# H0AR4_Backend.net
KiCad netlist of a schematic drawn in Altium Designer
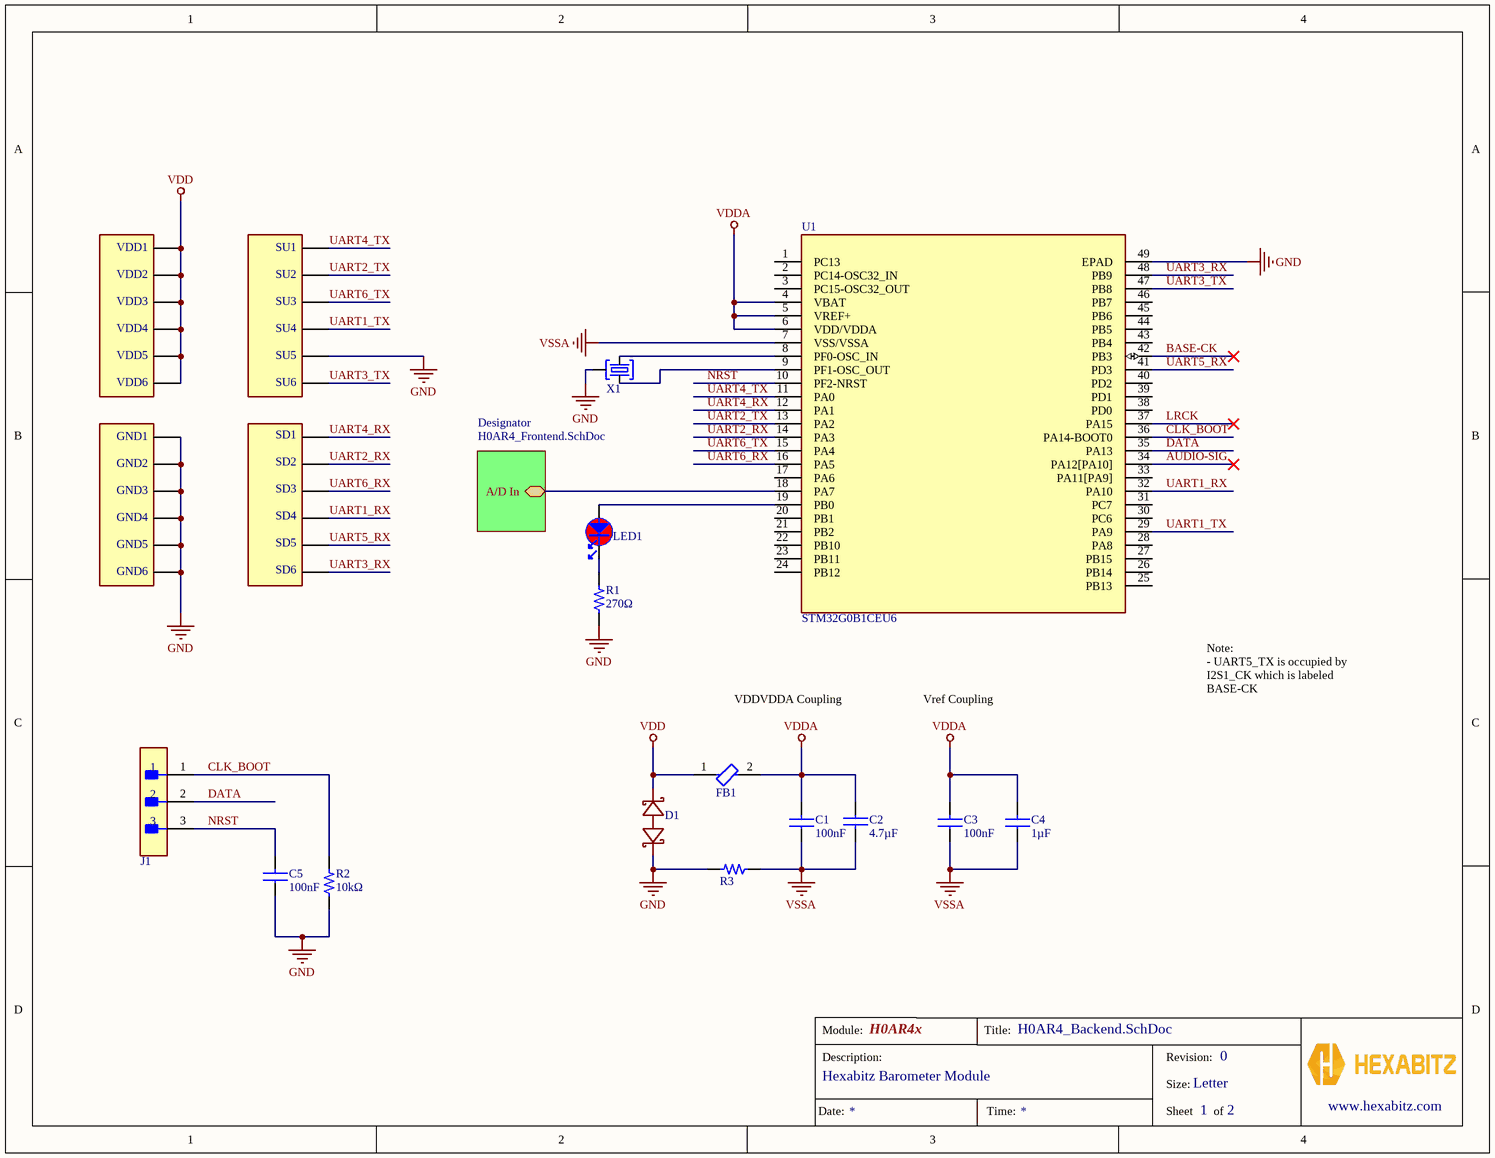
[diagram p0: H0AR4_Backend.SchDoc]

(export (version "E")
  (design (tool "Eeschema 10.0.6"))
  (components
    (comp (ref "C1")
      (value "100nF")
      (footprint "C0603")
      (fields
        (field (name "MANUFACTURER") "Samsung Electro-Mechanics")
        (field (name "MANUFACTURER PART NUMBER") "CL10B104KA8NNNC")
        (field (name "TOLERANCE") "10%")
      )
      (libsource (lib "Hexabitz Altium Library") (part "generic Capacitor"))
    )
    (comp (ref "C2")
      (value "4.7µF")
      (footprint "C0805")
      (fields
        (field (name "MANUFACTURER") "Samsung Electro-Mechanics")
        (field (name "MANUFACTURER PART NUMBER") "CL21X475KAQNNNE")
        (field (name "TOLERANCE") "10%")
      )
      (libsource (lib "Hexabitz Altium Library") (part "generic Capacitor"))
    )
    (comp (ref "C3")
      (value "100nF")
      (footprint "C0603")
      (fields
        (field (name "MANUFACTURER") "Samsung Electro-Mechanics")
        (field (name "MANUFACTURER PART NUMBER") "CL10B104KA8NNNC")
        (field (name "TOLERANCE") "10%")
      )
      (libsource (lib "Hexabitz Altium Library") (part "generic Capacitor"))
    )
    (comp (ref "C4")
      (value "1µF")
      (footprint "C0805")
      (description "Ceramic Capacitor, Ceramic, 16V, 10% +Tol, 10% -Tol, X7R, 15% TC, 1uF, Surface Mount, 0805")
      (fields
        (field (name "MANUFACTURER") "Yageo Group")
        (field (name "MANUFACTURER PART NUMBER") "CC0805KKX7R7BB105")
      )
      (libsource (lib "Hexabitz Altium Library") (part "generic Capacitor"))
    )
    (comp (ref "C5")
      (value "100nF")
      (footprint "C0603")
      (fields
        (field (name "MANUFACTURER") "Samsung Electro-Mechanics")
        (field (name "MANUFACTURER PART NUMBER") "CL10B104KA8NNNC")
        (field (name "TOLERANCE") "10%")
      )
      (libsource (lib "Hexabitz Altium Library") (part "generic Capacitor"))
    )
    (comp (ref "D1")
      (value "CDSOD323-T03SC")
      (footprint "SOD2513X114N")
      (description "A 3V, 350W, bi-directional, standard capacitance, SOD323 pkg TVS Diode ¦ Bourns CDSOD323-T03SC")
      (fields (field (name "MANUFACTURER") "Bourns"))
      (libsource (lib "Hexabitz Altium Library") (part "CDSOD323-T03SC"))
    )
    (comp (ref "FB1")
      (value "MMZ1608Y300B")
      (footprint "FP-MMZ1608-0_8-MFG")
      (description "Ferrite Beads 0603 30ohms 1500mA Signal Line AEC-Q200")
      (fields
        (field (name "MANUFACTURER") "TDK")
        (field (name "MANUFACTURER PART NUMBER") "MMZ1608Y300BTD25")
      )
      (libsource (lib "Hexabitz Altium Library") (part "MMZ1608Y300B"))
    )
    (comp (ref "GND1")
      (value "HEXABIT_UART_PORT")
      (footprint "HEXABIT_POWER_PORT_D")
      (libsource (lib "hexabitz_connectors.Library") (part "HEXABIT_POWER_PORT_D"))
    )
    (comp (ref "GND2")
      (value "HEXABIT_UART_PORT")
      (footprint "HEXABIT_POWER_PORT_D")
      (libsource (lib "hexabitz_connectors.Library") (part "HEXABIT_POWER_PORT_D"))
    )
    (comp (ref "GND3")
      (value "HEXABIT_UART_PORT")
      (footprint "HEXABIT_POWER_PORT_D")
      (libsource (lib "hexabitz_connectors.Library") (part "HEXABIT_POWER_PORT_D"))
    )
    (comp (ref "GND4")
      (value "HEXABIT_UART_PORT")
      (footprint "HEXABIT_POWER_PORT_D")
      (libsource (lib "hexabitz_connectors.Library") (part "HEXABIT_POWER_PORT_D"))
    )
    (comp (ref "GND5")
      (value "HEXABIT_UART_PORT")
      (footprint "HEXABIT_POWER_PORT_D")
      (libsource (lib "hexabitz_connectors.Library") (part "HEXABIT_POWER_PORT_D"))
    )
    (comp (ref "GND6")
      (value "HEXABIT_UART_PORT")
      (footprint "HEXABIT_POWER_PORT_D")
      (libsource (lib "hexabitz_connectors.Library") (part "HEXABIT_POWER_PORT_D"))
    )
    (comp (ref "J1")
      (value "TSW-103-14-G-S")
      (footprint "FP-TSW-103-14-G-S-MFG")
      (description "CONN HEADER VERT 3POS 2.54MM")
      (libsource (lib "Altium Content Vault") (part "cd3439d6ef35ae5d9b27ec4fdd3e828"))
    )
    (comp (ref "LED1")
      (value "VLMS1300-GS08")
      (footprint "FP-6_541-5092_01-4-MFG")
      (description "LED Uni-Color Super Red 639nm 2-Pin Chip 0603(1608Metric) T/R")
      (fields (field (name "MANUFACTURER") "Vishay Semiconductors"))
      (libsource (lib "Hexabitz Altium Library") (part "VLMS1300-GS08"))
    )
    (comp (ref "R1")
      (value "270Ω")
      (footprint "R0603")
      (description "Res Thick Film 0603 270 Ohm 5% 0.1W(1/10W) ±200ppm/C Pad SMD Automotive T/R")
      (fields
        (field (name "MANUFACTURER") "Panasonic")
        (field (name "MANUFACTURER PART NUMBER") "ERJ-3GEYJ271V")
      )
      (libsource (lib "") (part "generic Resistor_1"))
    )
    (comp (ref "R2")
      (value "10kΩ")
      (footprint "R0603")
      (description "100mW Thick Film Resistors ±100ppm/℃ ±1% 10kΩ 0603 Chip Resistor - Surface Mount ROHS")
      (fields
        (field (name "MANUFACTURER") "Yageo Group")
        (field (name "MANUFACTURER PART NUMBER") "RC0603FR-0710KL")
      )
      (libsource (lib "") (part "generic Resistor_2"))
    )
    (comp (ref "R3")
      (value "Manufacturer Part Number")
      (footprint "R0603")
      (libsource (lib "Hexabitz Altium Library") (part "generic Resistor"))
    )
    (comp (ref "SD1")
      (value "HEXABIT_UART_PORT")
      (footprint "HEXABIT_UART_PORT_D")
      (libsource (lib "hexabitz_connectors.Library") (part "HEXABIT_UART_PORT_D"))
    )
    (comp (ref "SD2")
      (value "HEXABIT_UART_PORT")
      (footprint "HEXABIT_UART_PORT_D")
      (libsource (lib "hexabitz_connectors.Library") (part "HEXABIT_UART_PORT_D"))
    )
    (comp (ref "SD3")
      (value "HEXABIT_UART_PORT")
      (footprint "HEXABIT_UART_PORT_D")
      (libsource (lib "hexabitz_connectors.Library") (part "HEXABIT_UART_PORT_D"))
    )
    (comp (ref "SD4")
      (value "HEXABIT_UART_PORT")
      (footprint "HEXABIT_UART_PORT_D")
      (libsource (lib "hexabitz_connectors.Library") (part "HEXABIT_UART_PORT_D"))
    )
    (comp (ref "SD5")
      (value "HEXABIT_UART_PORT")
      (footprint "HEXABIT_UART_PORT_D")
      (libsource (lib "hexabitz_connectors.Library") (part "HEXABIT_UART_PORT_D"))
    )
    (comp (ref "SD6")
      (value "HEXABIT_UART_PORT")
      (footprint "HEXABIT_UART_PORT_D")
      (libsource (lib "hexabitz_connectors.Library") (part "HEXABIT_UART_PORT_D"))
    )
    (comp (ref "SU1")
      (value "HEXABIT_UART_PORT")
      (footprint "HEXABIT_UART_PORT_U")
      (libsource (lib "hexabitz_connectors.Library") (part "HEXABIT_UART_PORT_U"))
    )
    (comp (ref "SU2")
      (value "HEXABIT_UART_PORT")
      (footprint "HEXABIT_UART_PORT_U")
      (libsource (lib "hexabitz_connectors.Library") (part "HEXABIT_UART_PORT_U"))
    )
    (comp (ref "SU3")
      (value "HEXABIT_UART_PORT")
      (footprint "HEXABIT_UART_PORT_U")
      (libsource (lib "hexabitz_connectors.Library") (part "HEXABIT_UART_PORT_U"))
    )
    (comp (ref "SU4")
      (value "HEXABIT_UART_PORT")
      (footprint "HEXABIT_UART_PORT_U")
      (libsource (lib "hexabitz_connectors.Library") (part "HEXABIT_UART_PORT_U"))
    )
    (comp (ref "SU5")
      (value "HEXABIT_UART_PORT")
      (footprint "HEXABIT_UART_PORT_U")
      (libsource (lib "hexabitz_connectors.Library") (part "HEXABIT_UART_PORT_U"))
    )
    (comp (ref "SU6")
      (value "HEXABIT_UART_PORT")
      (footprint "HEXABIT_UART_PORT_U")
      (libsource (lib "hexabitz_connectors.Library") (part "HEXABIT_UART_PORT_U"))
    )
    (comp (ref "U1")
      (value "STM32G0B1CEU6")
      (footprint "QFN50P700X700X65-49N-D")
      (description "MCU 32-bit ARM Cortex M0+ RISC 512KB Flash 1.8V/2.5V/3.3V 48-Pin UFQFPN EP Tray")
      (fields
        (field (name "MANUFACTURER") "STMicroelectronics")
        (field (name "MANUFACTURER PART NUMBER") "STM32G0B1CEU6")
      )
      (libsource (lib "Hexabitz Altium Library") (part "STM32G0B1CEU6"))
    )
    (comp (ref "VDD1")
      (value "HEXABIT_UART_PORT")
      (footprint "HEXABIT_POWER_PORT_U")
      (libsource (lib "hexabitz_connectors.Library") (part "HEXABIT_POWER_PORT_U"))
    )
    (comp (ref "VDD2")
      (value "HEXABIT_UART_PORT")
      (footprint "HEXABIT_POWER_PORT_U")
      (libsource (lib "hexabitz_connectors.Library") (part "HEXABIT_POWER_PORT_U"))
    )
    (comp (ref "VDD3")
      (value "HEXABIT_UART_PORT")
      (footprint "HEXABIT_POWER_PORT_U")
      (libsource (lib "hexabitz_connectors.Library") (part "HEXABIT_POWER_PORT_U"))
    )
    (comp (ref "VDD4")
      (value "HEXABIT_UART_PORT")
      (footprint "HEXABIT_POWER_PORT_U")
      (libsource (lib "hexabitz_connectors.Library") (part "HEXABIT_POWER_PORT_U"))
    )
    (comp (ref "VDD5")
      (value "HEXABIT_UART_PORT")
      (footprint "HEXABIT_POWER_PORT_U")
      (libsource (lib "hexabitz_connectors.Library") (part "HEXABIT_POWER_PORT_U"))
    )
    (comp (ref "VDD6")
      (value "HEXABIT_UART_PORT")
      (footprint "HEXABIT_POWER_PORT_U")
      (libsource (lib "hexabitz_connectors.Library") (part "HEXABIT_POWER_PORT_U"))
    )
    (comp (ref "X1")
      (value "CSTCE8M00G52Z-R0")
      (footprint "XTALL_CSTCE8M00G52")
      (description "Ceramic Resonator 8MHz ±0.5% (Tol) ±0.2% (Stability) 10pF 40Ohm 3-Pin CSMD T/R")
      (fields (field (name "MANUFACTURER") "Murata") (field (name "TOLERANCE") "0.5%"))
      (libsource (lib "Hexabitz Altium Library") (part "CSTCE8M00G52Z-R0"))
    )
  )
  (nets
    (net (code "1") (name "/AUDIO-SIG") (class "Default")
      (node (ref "U1") (pin "34") (pinfunction "PA12[PA10]_34") (pintype "passive+no_connect"))
    )
    (net (code "2") (name "/A{slash}D In") (class "Default")
      (node (ref "U1") (pin "18") (pinfunction "PA7_18") (pintype "passive"))
    )
    (net (code "3") (name "/BASE-CK") (class "Default")
      (node (ref "U1") (pin "42") (pinfunction "PB3_42") (pintype "bidirectional+no_connect"))
    )
    (net (code "4") (name "/CLK_BOOT") (class "Default")
      (node (ref "J1") (pin "1") (pinfunction "1_1") (pintype "passive"))
      (node (ref "R2") (pin "1") (pinfunction "1_1") (pintype "passive"))
      (node (ref "U1") (pin "36") (pinfunction "PA14-BOOT0_36") (pintype "passive"))
    )
    (net (code "5") (name "/DATA") (class "Default")
      (node (ref "J1") (pin "2") (pinfunction "2_2") (pintype "passive"))
      (node (ref "U1") (pin "35") (pinfunction "PA13_35") (pintype "passive"))
    )
    (net (code "6") (name "/LRCK") (class "Default")
      (node (ref "U1") (pin "37") (pinfunction "PA15_37") (pintype "passive+no_connect"))
    )
    (net (code "7") (name "/NRST") (class "Default")
      (node (ref "C5") (pin "2") (pinfunction "2_2") (pintype "passive"))
      (node (ref "J1") (pin "3") (pinfunction "3_3") (pintype "passive"))
      (node (ref "U1") (pin "10") (pinfunction "PF2-NRST_10") (pintype "passive"))
    )
    (net (code "8") (name "/UART1_RX") (class "Default")
      (node (ref "SD4") (pin "UART_D") (pinfunction "UART_D_UART_D") (pintype "passive"))
      (node (ref "U1") (pin "32") (pinfunction "PA10_32") (pintype "passive"))
    )
    (net (code "9") (name "/UART1_TX") (class "Default")
      (node (ref "SU4") (pin "UART_U") (pinfunction "UART_U_UART_U") (pintype "passive"))
      (node (ref "U1") (pin "29") (pinfunction "PA9_29") (pintype "passive"))
    )
    (net (code "10") (name "/UART2_RX") (class "Default")
      (node (ref "SD2") (pin "UART_D") (pinfunction "UART_D_UART_D") (pintype "passive"))
      (node (ref "U1") (pin "14") (pinfunction "PA3_14") (pintype "passive"))
    )
    (net (code "11") (name "/UART2_TX") (class "Default")
      (node (ref "SU2") (pin "UART_U") (pinfunction "UART_U_UART_U") (pintype "passive"))
      (node (ref "U1") (pin "13") (pinfunction "PA2_13") (pintype "passive"))
    )
    (net (code "12") (name "/UART3_RX") (class "Default")
      (node (ref "SD6") (pin "UART_D") (pinfunction "UART_D_UART_D") (pintype "passive"))
      (node (ref "U1") (pin "48") (pinfunction "PB9_48") (pintype "passive"))
    )
    (net (code "13") (name "/UART3_TX") (class "Default")
      (node (ref "SU6") (pin "UART_U") (pinfunction "UART_U_UART_U") (pintype "passive"))
      (node (ref "U1") (pin "47") (pinfunction "PB8_47") (pintype "passive"))
    )
    (net (code "14") (name "/UART4_RX") (class "Default")
      (node (ref "SD1") (pin "UART_D") (pinfunction "UART_D_UART_D") (pintype "passive"))
      (node (ref "U1") (pin "12") (pinfunction "PA1_12") (pintype "passive"))
    )
    (net (code "15") (name "/UART4_TX") (class "Default")
      (node (ref "SU1") (pin "UART_U") (pinfunction "UART_U_UART_U") (pintype "passive"))
      (node (ref "U1") (pin "11") (pinfunction "PA0_11") (pintype "passive"))
    )
    (net (code "16") (name "/UART5_RX") (class "Default")
      (node (ref "SD5") (pin "UART_D") (pinfunction "UART_D_UART_D") (pintype "passive"))
      (node (ref "U1") (pin "41") (pinfunction "PD3_41") (pintype "passive"))
    )
    (net (code "17") (name "/UART6_RX") (class "Default")
      (node (ref "SD3") (pin "UART_D") (pinfunction "UART_D_UART_D") (pintype "passive"))
      (node (ref "U1") (pin "16") (pinfunction "PA5_16") (pintype "passive"))
    )
    (net (code "18") (name "/UART6_TX") (class "Default")
      (node (ref "SU3") (pin "UART_U") (pinfunction "UART_U_UART_U") (pintype "passive"))
      (node (ref "U1") (pin "15") (pinfunction "PA4_15") (pintype "passive"))
    )
    (net (code "19") (name "GND") (class "Default")
      (node (ref "C5") (pin "1") (pinfunction "1_1") (pintype "passive"))
      (node (ref "D1") (pin "1") (pinfunction "A_1") (pintype "passive"))
      (node (ref "GND1") (pin "Pwr_D") (pinfunction "Pwr_D_Pwr_D") (pintype "passive"))
      (node (ref "GND2") (pin "Pwr_D") (pinfunction "Pwr_D_Pwr_D") (pintype "passive"))
      (node (ref "GND3") (pin "Pwr_D") (pinfunction "Pwr_D_Pwr_D") (pintype "passive"))
      (node (ref "GND4") (pin "Pwr_D") (pinfunction "Pwr_D_Pwr_D") (pintype "passive"))
      (node (ref "GND5") (pin "Pwr_D") (pinfunction "Pwr_D_Pwr_D") (pintype "passive"))
      (node (ref "GND6") (pin "Pwr_D") (pinfunction "Pwr_D_Pwr_D") (pintype "passive"))
      (node (ref "R1") (pin "1") (pinfunction "1_1") (pintype "passive"))
      (node (ref "R2") (pin "2") (pinfunction "2_2") (pintype "passive"))
      (node (ref "R3") (pin "1") (pinfunction "1_1") (pintype "passive"))
      (node (ref "SU5") (pin "UART_U") (pinfunction "UART_U_UART_U") (pintype "passive"))
      (node (ref "U1") (pin "49") (pinfunction "EPAD_49") (pintype "passive"))
      (node (ref "X1") (pin "P$2") (pinfunction "2_P$2") (pintype "passive"))
    )
    (net (code "20") (name "Net-(LED1-Pad1)") (class "Default")
      (node (ref "LED1") (pin "1") (pintype "passive"))
      (node (ref "R1") (pin "2") (pinfunction "2_2") (pintype "passive"))
    )
    (net (code "21") (name "Net-(U1-PB0)") (class "Default")
      (node (ref "LED1") (pin "2") (pintype "passive"))
      (node (ref "U1") (pin "19") (pinfunction "PB0_19") (pintype "passive"))
    )
    (net (code "22") (name "Net-(U1-PF0-OSC_IN)") (class "Default")
      (node (ref "U1") (pin "8") (pinfunction "PF0-OSC_IN_8") (pintype "passive"))
      (node (ref "X1") (pin "P$3") (pinfunction "3_P$3") (pintype "passive"))
    )
    (net (code "23") (name "Net-(U1-PF1-OSC_OUT)") (class "Default")
      (node (ref "U1") (pin "9") (pinfunction "PF1-OSC_OUT_9") (pintype "passive"))
      (node (ref "X1") (pin "P$1") (pinfunction "1_P$1") (pintype "passive"))
    )
    (net (code "24") (name "VDD") (class "Default")
      (node (ref "D1") (pin "2") (pinfunction "C_2") (pintype "passive"))
      (node (ref "FB1") (pin "1") (pinfunction "1_1") (pintype "passive"))
      (node (ref "VDD1") (pin "Pwr_U") (pinfunction "Pwr_U_Pwr_U") (pintype "passive"))
      (node (ref "VDD2") (pin "Pwr_U") (pinfunction "Pwr_U_Pwr_U") (pintype "passive"))
      (node (ref "VDD3") (pin "Pwr_U") (pinfunction "Pwr_U_Pwr_U") (pintype "passive"))
      (node (ref "VDD4") (pin "Pwr_U") (pinfunction "Pwr_U_Pwr_U") (pintype "passive"))
      (node (ref "VDD5") (pin "Pwr_U") (pinfunction "Pwr_U_Pwr_U") (pintype "passive"))
      (node (ref "VDD6") (pin "Pwr_U") (pinfunction "Pwr_U_Pwr_U") (pintype "passive"))
    )
    (net (code "25") (name "VDDA") (class "Default")
      (node (ref "C1") (pin "2") (pinfunction "2_2") (pintype "passive"))
      (node (ref "C2") (pin "1") (pinfunction "1_1") (pintype "passive"))
      (node (ref "C3") (pin "2") (pinfunction "2_2") (pintype "passive"))
      (node (ref "C4") (pin "2") (pinfunction "2_2") (pintype "passive"))
      (node (ref "FB1") (pin "2") (pinfunction "2_2") (pintype "passive"))
      (node (ref "U1") (pin "4") (pinfunction "VBAT_4") (pintype "passive"))
      (node (ref "U1") (pin "5") (pinfunction "VREF+_5") (pintype "passive"))
      (node (ref "U1") (pin "6") (pinfunction "VDD/VDDA_6") (pintype "passive"))
    )
    (net (code "26") (name "VSSA") (class "Default")
      (node (ref "C1") (pin "1") (pinfunction "1_1") (pintype "passive"))
      (node (ref "C2") (pin "2") (pinfunction "2_2") (pintype "passive"))
      (node (ref "C3") (pin "1") (pinfunction "1_1") (pintype "passive"))
      (node (ref "C4") (pin "1") (pinfunction "1_1") (pintype "passive"))
      (node (ref "R3") (pin "2") (pinfunction "2_2") (pintype "passive"))
      (node (ref "U1") (pin "7") (pinfunction "VSS/VSSA_7") (pintype "passive"))
    )
    (net (code "27") (name "unconnected-(U1-PA6-Pad17)") (class "Default")
      (node (ref "U1") (pin "17") (pinfunction "PA6_17") (pintype "passive"))
    )
    (net (code "28") (name "unconnected-(U1-PA8-Pad28)") (class "Default")
      (node (ref "U1") (pin "28") (pinfunction "PA8_28") (pintype "passive"))
    )
    (net (code "29") (name "unconnected-(U1-PA11[PA9]-Pad33)") (class "Default")
      (node (ref "U1") (pin "33") (pinfunction "PA11[PA9]_33") (pintype "passive"))
    )
    (net (code "30") (name "unconnected-(U1-PB1-Pad20)") (class "Default")
      (node (ref "U1") (pin "20") (pinfunction "PB1_20") (pintype "passive"))
    )
    (net (code "31") (name "unconnected-(U1-PB2-Pad21)") (class "Default")
      (node (ref "U1") (pin "21") (pinfunction "PB2_21") (pintype "passive"))
    )
    (net (code "32") (name "unconnected-(U1-PB4-Pad43)") (class "Default")
      (node (ref "U1") (pin "43") (pinfunction "PB4_43") (pintype "passive"))
    )
    (net (code "33") (name "unconnected-(U1-PB5-Pad44)") (class "Default")
      (node (ref "U1") (pin "44") (pinfunction "PB5_44") (pintype "passive"))
    )
    (net (code "34") (name "unconnected-(U1-PB6-Pad45)") (class "Default")
      (node (ref "U1") (pin "45") (pinfunction "PB6_45") (pintype "passive"))
    )
    (net (code "35") (name "unconnected-(U1-PB7-Pad46)") (class "Default")
      (node (ref "U1") (pin "46") (pinfunction "PB7_46") (pintype "passive"))
    )
    (net (code "36") (name "unconnected-(U1-PB10-Pad22)") (class "Default")
      (node (ref "U1") (pin "22") (pinfunction "PB10_22") (pintype "passive"))
    )
    (net (code "37") (name "unconnected-(U1-PB11-Pad23)") (class "Default")
      (node (ref "U1") (pin "23") (pinfunction "PB11_23") (pintype "passive"))
    )
    (net (code "38") (name "unconnected-(U1-PB12-Pad24)") (class "Default")
      (node (ref "U1") (pin "24") (pinfunction "PB12_24") (pintype "passive"))
    )
    (net (code "39") (name "unconnected-(U1-PB13-Pad25)") (class "Default")
      (node (ref "U1") (pin "25") (pinfunction "PB13_25") (pintype "passive"))
    )
    (net (code "40") (name "unconnected-(U1-PB14-Pad26)") (class "Default")
      (node (ref "U1") (pin "26") (pinfunction "PB14_26") (pintype "passive"))
    )
    (net (code "41") (name "unconnected-(U1-PB15-Pad27)") (class "Default")
      (node (ref "U1") (pin "27") (pinfunction "PB15_27") (pintype "passive"))
    )
    (net (code "42") (name "unconnected-(U1-PC6-Pad30)") (class "Default")
      (node (ref "U1") (pin "30") (pinfunction "PC6_30") (pintype "passive"))
    )
    (net (code "43") (name "unconnected-(U1-PC7-Pad31)") (class "Default")
      (node (ref "U1") (pin "31") (pinfunction "PC7_31") (pintype "passive"))
    )
    (net (code "44") (name "unconnected-(U1-PC13-Pad1)") (class "Default")
      (node (ref "U1") (pin "1") (pinfunction "PC13_1") (pintype "passive"))
    )
    (net (code "45") (name "unconnected-(U1-PC14-OSC32_IN-Pad2)") (class "Default")
      (node (ref "U1") (pin "2") (pinfunction "PC14-OSC32_IN_2") (pintype "passive"))
    )
    (net (code "46") (name "unconnected-(U1-PC15-OSC32_OUT-Pad3)") (class "Default")
      (node (ref "U1") (pin "3") (pinfunction "PC15-OSC32_OUT_3") (pintype "passive"))
    )
    (net (code "47") (name "unconnected-(U1-PD0-Pad38)") (class "Default")
      (node (ref "U1") (pin "38") (pinfunction "PD0_38") (pintype "passive"))
    )
    (net (code "48") (name "unconnected-(U1-PD1-Pad39)") (class "Default")
      (node (ref "U1") (pin "39") (pinfunction "PD1_39") (pintype "passive"))
    )
    (net (code "49") (name "unconnected-(U1-PD2-Pad40)") (class "Default")
      (node (ref "U1") (pin "40") (pinfunction "PD2_40") (pintype "passive"))
    )
  )
)
